# C64_PSU_230_115.net
KiCad netlist of a schematic drawn in EAGLE
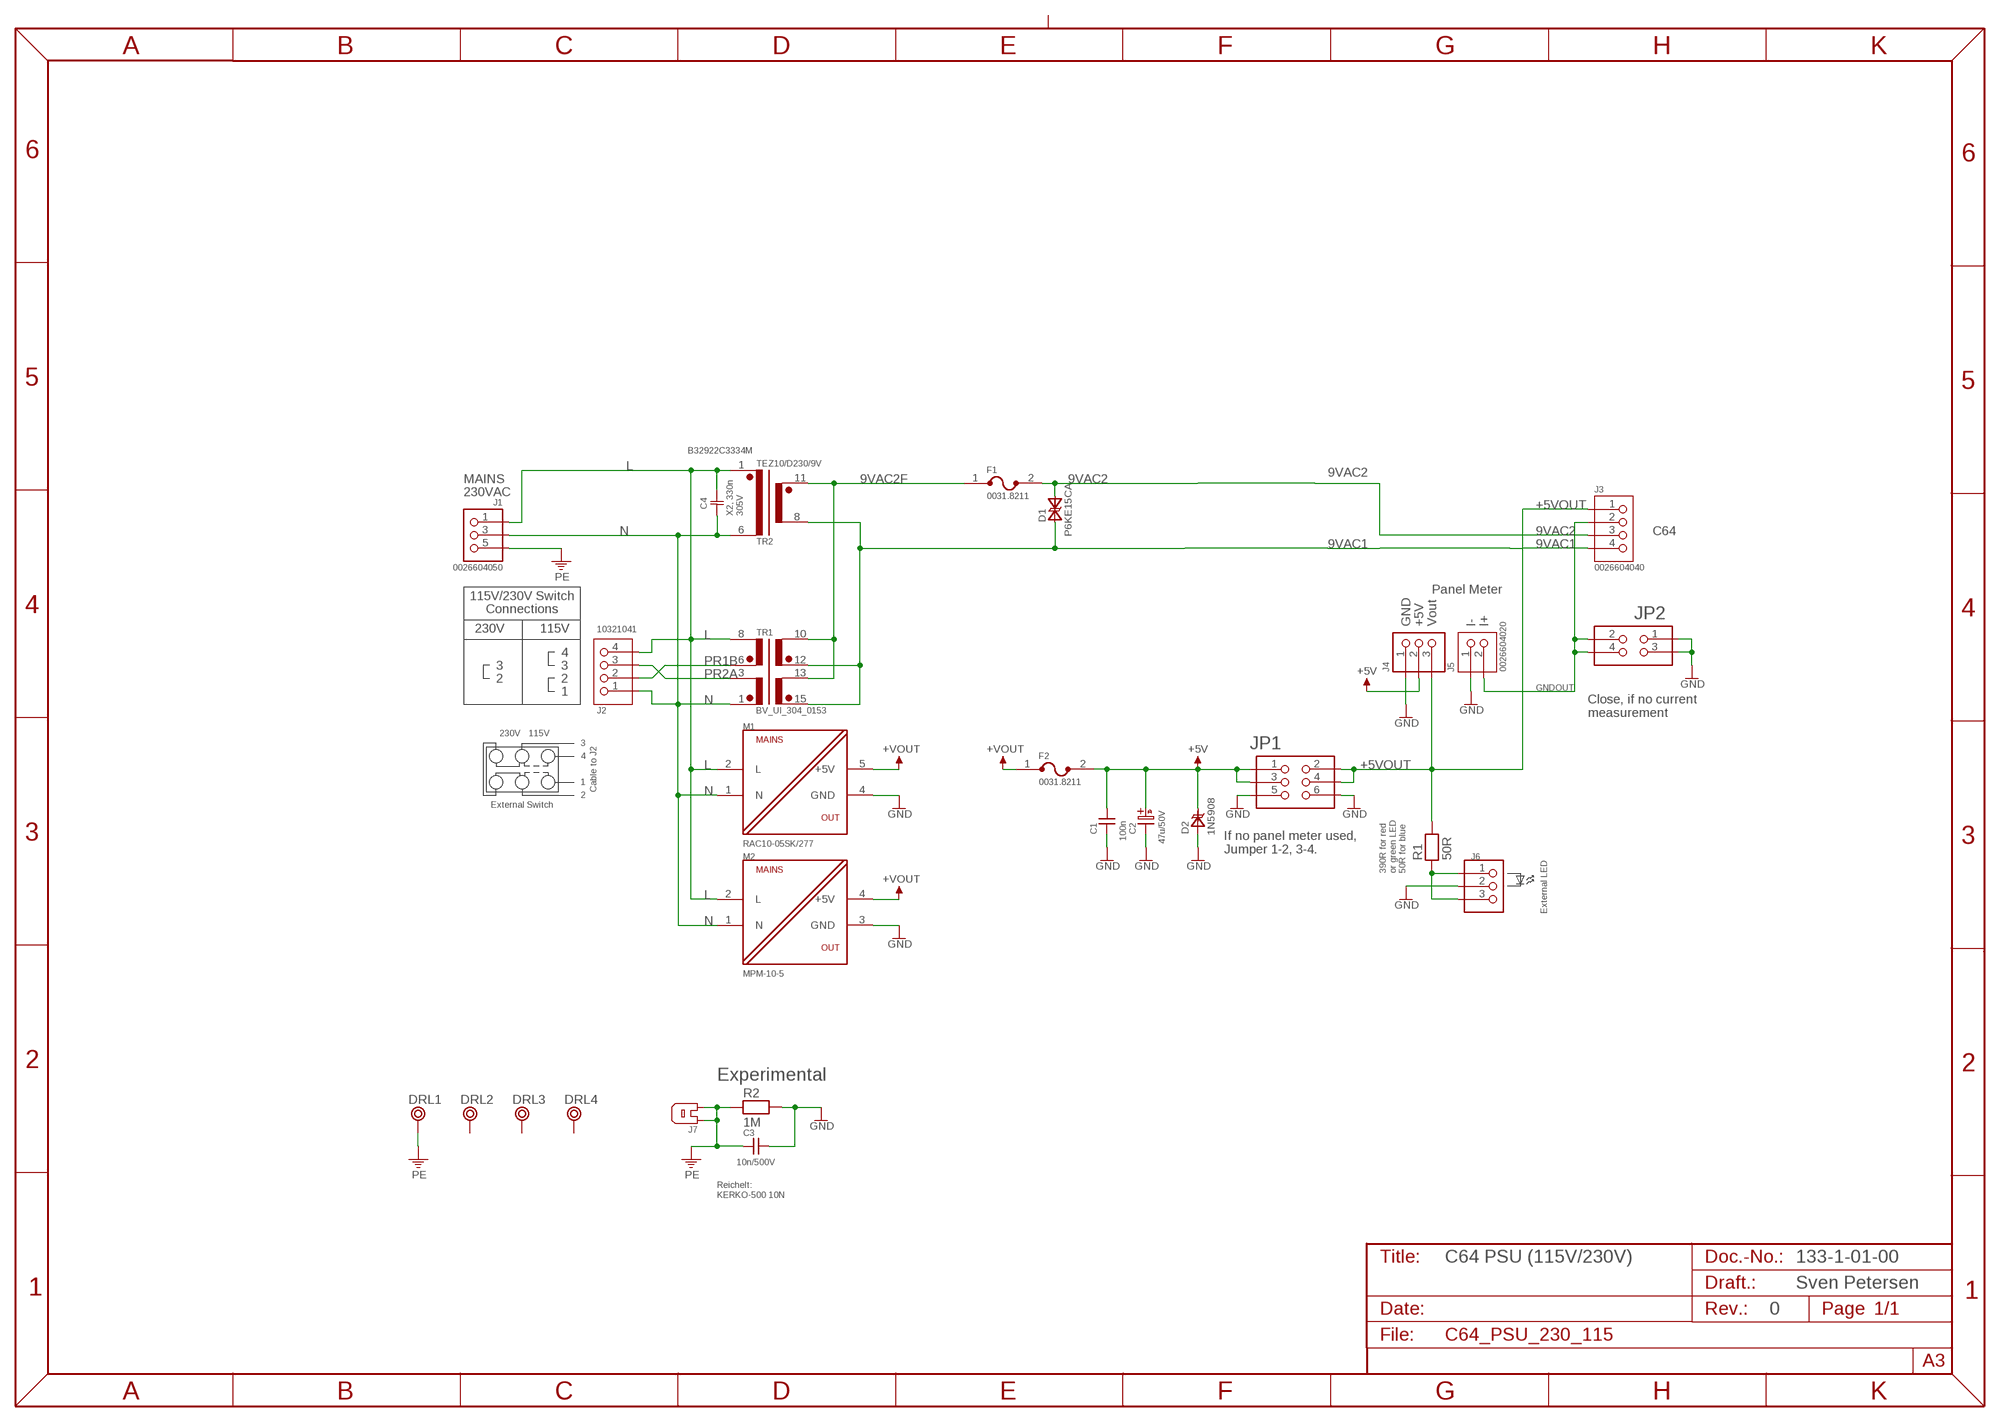
[diagram p0: schematic, sheet 1]

(export (version "E")
  (design (tool "Eeschema 10.0.6"))
  (components
    (comp (ref "C1")
      (value "100n")
      (footprint "eagle-import:C-2,5")
      (libsource (lib "eagle-import") (part "CAP01"))
    )
    (comp (ref "C2")
      (value "47u/50V")
      (footprint "eagle-import:C07_2,5")
      (libsource (lib "eagle-import") (part "C07/2,5"))
    )
    (comp (ref "C3")
      (value "10n/500V")
      (footprint "eagle-import:C-5")
      (libsource (lib "eagle-import") (part "CAP02"))
    )
    (comp (ref "C4")
      (value "B32922C3334M")
      (footprint "eagle-import:C-18X8-RM15")
      (libsource (lib "eagle-import") (part "X2--RM15-18X8"))
    )
    (comp (ref "D1")
      (value "P6KE15CA")
      (footprint "eagle-import:CB417NP")
      (libsource (lib "eagle-import") (part "P6KE15CA"))
    )
    (comp (ref "D2")
      (value "1N5908")
      (footprint "eagle-import:CB429")
      (libsource (lib "eagle-import") (part "1N5908"))
    )
    (comp (ref "DRL1")
      (value "BOHR3,5OR")
      (footprint "eagle-import:BOHR3,5_OHNE_RESTRICT")
      (libsource (lib "eagle-import") (part "BOHR3,5OR"))
    )
    (comp (ref "DRL2")
      (value "BOHR3,5")
      (footprint "eagle-import:BOHR3,5")
      (libsource (lib "eagle-import") (part "BOHR3,5"))
    )
    (comp (ref "DRL3")
      (value "BOHR3,5")
      (footprint "eagle-import:BOHR3,5")
      (libsource (lib "eagle-import") (part "BOHR3,5"))
    )
    (comp (ref "DRL4")
      (value "BOHR3,5")
      (footprint "eagle-import:BOHR3,5")
      (libsource (lib "eagle-import") (part "BOHR3,5"))
    )
    (comp (ref "F1")
      (value "0031.8211")
      (footprint "eagle-import:0031.8211")
      (libsource (lib "eagle-import") (part "0031.8211"))
    )
    (comp (ref "F2")
      (value "0031.8211")
      (footprint "eagle-import:0031.8211")
      (libsource (lib "eagle-import") (part "0031.8211"))
    )
    (comp (ref "J1")
      (value "0026604050")
      (footprint "eagle-import:SPOX_3.96_5P3")
      (libsource (lib "eagle-import") (part "0026604050MOD"))
    )
    (comp (ref "J2")
      (value "10321041")
      (footprint "eagle-import:SPOX_5.08_4P")
      (libsource (lib "eagle-import") (part "10321041"))
    )
    (comp (ref "J3")
      (value "0026604040")
      (footprint "eagle-import:SPOX_3.96_4P")
      (libsource (lib "eagle-import") (part "0026604040"))
    )
    (comp (ref "J4")
      (value "6410-3P")
      (footprint "eagle-import:6410-3P")
      (libsource (lib "eagle-import") (part "6410-3P"))
    )
    (comp (ref "J5")
      (value "0026604020")
      (footprint "eagle-import:SPOX_3.96_2P")
      (libsource (lib "eagle-import") (part "0026604020"))
    )
    (comp (ref "J6")
      (value "PINHD-1X3")
      (footprint "eagle-import:1X03")
      (libsource (lib "eagle-import") (part "PINHD-1X3"))
    )
    (comp (ref "J7")
      (value "FLA6,3")
      (footprint "eagle-import:FLA6,3")
      (libsource (lib "eagle-import") (part "FLA6,3"))
    )
    (comp (ref "JP1")
      (value "PINHD-2X3")
      (footprint "eagle-import:2X03")
      (libsource (lib "eagle-import") (part "PINHD-2X3"))
    )
    (comp (ref "JP2")
      (value "PINHD-2X2")
      (footprint "eagle-import:2X02")
      (libsource (lib "eagle-import") (part "PINHD-2X2"))
    )
    (comp (ref "M1")
      (value "RAC10-05SK/277")
      (footprint "eagle-import:RAC10-K_277")
      (libsource (lib "eagle-import") (part "RAC10-05SK/277"))
    )
    (comp (ref "M2")
      (value "MPM-10-5")
      (footprint "eagle-import:MPM10")
      (libsource (lib "eagle-import") (part "MPM-10-5"))
    )
    (comp (ref "R1")
      (value "50R")
      (footprint "eagle-import:R-10")
      (libsource (lib "eagle-import") (part "RES04"))
    )
    (comp (ref "R2")
      (value "1M")
      (footprint "eagle-import:R-10")
      (libsource (lib "eagle-import") (part "RES04"))
    )
    (comp (ref "TR1")
      (value "BV_UI_304_0153")
      (footprint "eagle-import:UI30")
      (libsource (lib "eagle-import") (part "BV_UI_304_0153"))
    )
    (comp (ref "TR2")
      (value "TEZ10/D230/9V")
      (footprint "eagle-import:TEZ10")
      (libsource (lib "eagle-import") (part "TEZ10/D230/9V"))
    )
  )
  (nets
    (net (code "1") (name "+5V") (class "Default")
      (node (ref "C1") (pin "2") (pinfunction "2_2") (pintype "passive"))
      (node (ref "C2") (pin "A") (pinfunction "+_A") (pintype "passive"))
      (node (ref "D2") (pin "K") (pinfunction "K_K") (pintype "passive"))
      (node (ref "F2") (pin "2") (pinfunction "2_2") (pintype "passive"))
      (node (ref "J4") (pin "2") (pinfunction "2_2") (pintype "passive"))
      (node (ref "JP1") (pin "1") (pinfunction "1_1") (pintype "passive"))
      (node (ref "JP1") (pin "3") (pinfunction "3_3") (pintype "passive"))
    )
    (net (code "2") (name "+VOUT") (class "Default")
      (node (ref "F2") (pin "1") (pinfunction "1_1") (pintype "passive"))
      (node (ref "M1") (pin "5") (pinfunction "+5V_5") (pintype "power_in"))
      (node (ref "M2") (pin "4") (pinfunction "+5V_4") (pintype "power_in"))
    )
    (net (code "3") (name "/+5VOUT") (class "Default")
      (node (ref "J3") (pin "1") (pinfunction "1_1") (pintype "passive"))
      (node (ref "J4") (pin "3") (pinfunction "3_3") (pintype "passive"))
      (node (ref "JP1") (pin "2") (pinfunction "2_2") (pintype "passive"))
      (node (ref "JP1") (pin "4") (pinfunction "4_4") (pintype "passive"))
      (node (ref "R1") (pin "2") (pinfunction "2_2") (pintype "passive"))
    )
    (net (code "4") (name "/9VAC1") (class "Default")
      (node (ref "D1") (pin "A") (pinfunction "A1_A") (pintype "passive"))
      (node (ref "J3") (pin "4") (pinfunction "4_4") (pintype "passive"))
      (node (ref "TR1") (pin "12") (pinfunction "SEC1B_12") (pintype "passive"))
      (node (ref "TR1") (pin "15") (pinfunction "SEC2B_15") (pintype "passive"))
      (node (ref "TR2") (pin "8") (pinfunction "SEC11_8") (pintype "passive"))
    )
    (net (code "5") (name "/9VAC2") (class "Default")
      (node (ref "D1") (pin "K") (pinfunction "A2_K") (pintype "passive"))
      (node (ref "F1") (pin "2") (pinfunction "2_2") (pintype "passive"))
      (node (ref "J3") (pin "3") (pinfunction "3_3") (pintype "passive"))
    )
    (net (code "6") (name "/9VAC2F") (class "Default")
      (node (ref "F1") (pin "1") (pinfunction "1_1") (pintype "passive"))
      (node (ref "TR1") (pin "10") (pinfunction "SEC1A_10") (pintype "passive"))
      (node (ref "TR1") (pin "13") (pinfunction "SEC2A_13") (pintype "passive"))
      (node (ref "TR2") (pin "11") (pinfunction "SEC12_11") (pintype "passive"))
    )
    (net (code "7") (name "/GNDOUT") (class "Default")
      (node (ref "J3") (pin "2") (pinfunction "2_2") (pintype "passive"))
      (node (ref "J5") (pin "2") (pinfunction "2_2") (pintype "passive"))
      (node (ref "JP2") (pin "2") (pinfunction "2_2") (pintype "passive"))
      (node (ref "JP2") (pin "4") (pinfunction "4_4") (pintype "passive"))
    )
    (net (code "8") (name "/L") (class "Default")
      (node (ref "C4") (pin "2") (pinfunction "2_2") (pintype "passive"))
      (node (ref "J1") (pin "1") (pinfunction "1_1") (pintype "passive"))
      (node (ref "J2") (pin "4") (pinfunction "4_4") (pintype "passive"))
      (node (ref "M1") (pin "2") (pinfunction "L_2") (pintype "power_in"))
      (node (ref "M2") (pin "2") (pinfunction "L_2") (pintype "power_in"))
      (node (ref "TR1") (pin "8") (pinfunction "PRI1A_8") (pintype "passive"))
      (node (ref "TR2") (pin "1") (pinfunction "PRI2_1") (pintype "passive"))
    )
    (net (code "9") (name "/N") (class "Default")
      (node (ref "C4") (pin "1") (pinfunction "1_1") (pintype "passive"))
      (node (ref "J1") (pin "3") (pinfunction "2_3") (pintype "passive"))
      (node (ref "J2") (pin "1") (pinfunction "1_1") (pintype "passive"))
      (node (ref "M1") (pin "1") (pinfunction "N_1") (pintype "power_in"))
      (node (ref "M2") (pin "1") (pinfunction "N_1") (pintype "power_in"))
      (node (ref "TR1") (pin "1") (pinfunction "PRI2B_1") (pintype "passive"))
      (node (ref "TR2") (pin "6") (pinfunction "PRI1_6") (pintype "passive"))
    )
    (net (code "10") (name "/PR1B") (class "Default")
      (node (ref "J2") (pin "2") (pinfunction "2_2") (pintype "passive"))
      (node (ref "TR1") (pin "6") (pinfunction "PRI1B_6") (pintype "passive"))
    )
    (net (code "11") (name "/PR2A") (class "Default")
      (node (ref "J2") (pin "3") (pinfunction "3_3") (pintype "passive"))
      (node (ref "TR1") (pin "3") (pinfunction "PRI2A_3") (pintype "passive"))
    )
    (net (code "12") (name "GND") (class "Default")
      (node (ref "C1") (pin "1") (pinfunction "1_1") (pintype "passive"))
      (node (ref "C2") (pin "K") (pinfunction "-_K") (pintype "passive"))
      (node (ref "C3") (pin "2") (pinfunction "2_2") (pintype "passive"))
      (node (ref "D2") (pin "A") (pinfunction "A_A") (pintype "passive"))
      (node (ref "J4") (pin "1") (pinfunction "1_1") (pintype "passive"))
      (node (ref "J5") (pin "1") (pinfunction "1_1") (pintype "passive"))
      (node (ref "J6") (pin "2") (pinfunction "2_2") (pintype "passive"))
      (node (ref "JP1") (pin "5") (pinfunction "5_5") (pintype "passive"))
      (node (ref "JP1") (pin "6") (pinfunction "6_6") (pintype "passive"))
      (node (ref "JP2") (pin "1") (pinfunction "1_1") (pintype "passive"))
      (node (ref "JP2") (pin "3") (pinfunction "3_3") (pintype "passive"))
      (node (ref "M1") (pin "4") (pinfunction "GND_4") (pintype "power_in"))
      (node (ref "M2") (pin "3") (pinfunction "GND_3") (pintype "power_in"))
      (node (ref "R2") (pin "2") (pinfunction "2_2") (pintype "passive"))
    )
    (net (code "13") (name "Net-(J6-Pad1)") (class "Default")
      (node (ref "J6") (pin "1") (pinfunction "1_1") (pintype "passive"))
      (node (ref "J6") (pin "3") (pinfunction "3_3") (pintype "passive"))
      (node (ref "R1") (pin "1") (pinfunction "1_1") (pintype "passive"))
    )
    (net (code "14") (name "PE") (class "Default")
      (node (ref "C3") (pin "1") (pinfunction "1_1") (pintype "passive"))
      (node (ref "DRL1") (pin "P$1") (pinfunction "P$1_P$1") (pintype "passive"))
      (node (ref "J1") (pin "5") (pinfunction "3_5") (pintype "passive"))
      (node (ref "J7") (pin "1") (pinfunction "1_1") (pintype "passive"))
      (node (ref "J7") (pin "2") (pinfunction "2_2") (pintype "passive"))
      (node (ref "R2") (pin "1") (pinfunction "1_1") (pintype "passive"))
    )
    (net (code "15") (name "unconnected-(DRL2-PadP$1)") (class "Default")
      (node (ref "DRL2") (pin "P$1") (pinfunction "P$1_P$1") (pintype "passive"))
    )
    (net (code "16") (name "unconnected-(DRL3-PadP$1)") (class "Default")
      (node (ref "DRL3") (pin "P$1") (pinfunction "P$1_P$1") (pintype "passive"))
    )
    (net (code "17") (name "unconnected-(DRL4-PadP$1)") (class "Default")
      (node (ref "DRL4") (pin "P$1") (pinfunction "P$1_P$1") (pintype "passive"))
    )
  )
)
